# school_shield.net
KiCad netlist of a schematic drawn in EAGLE
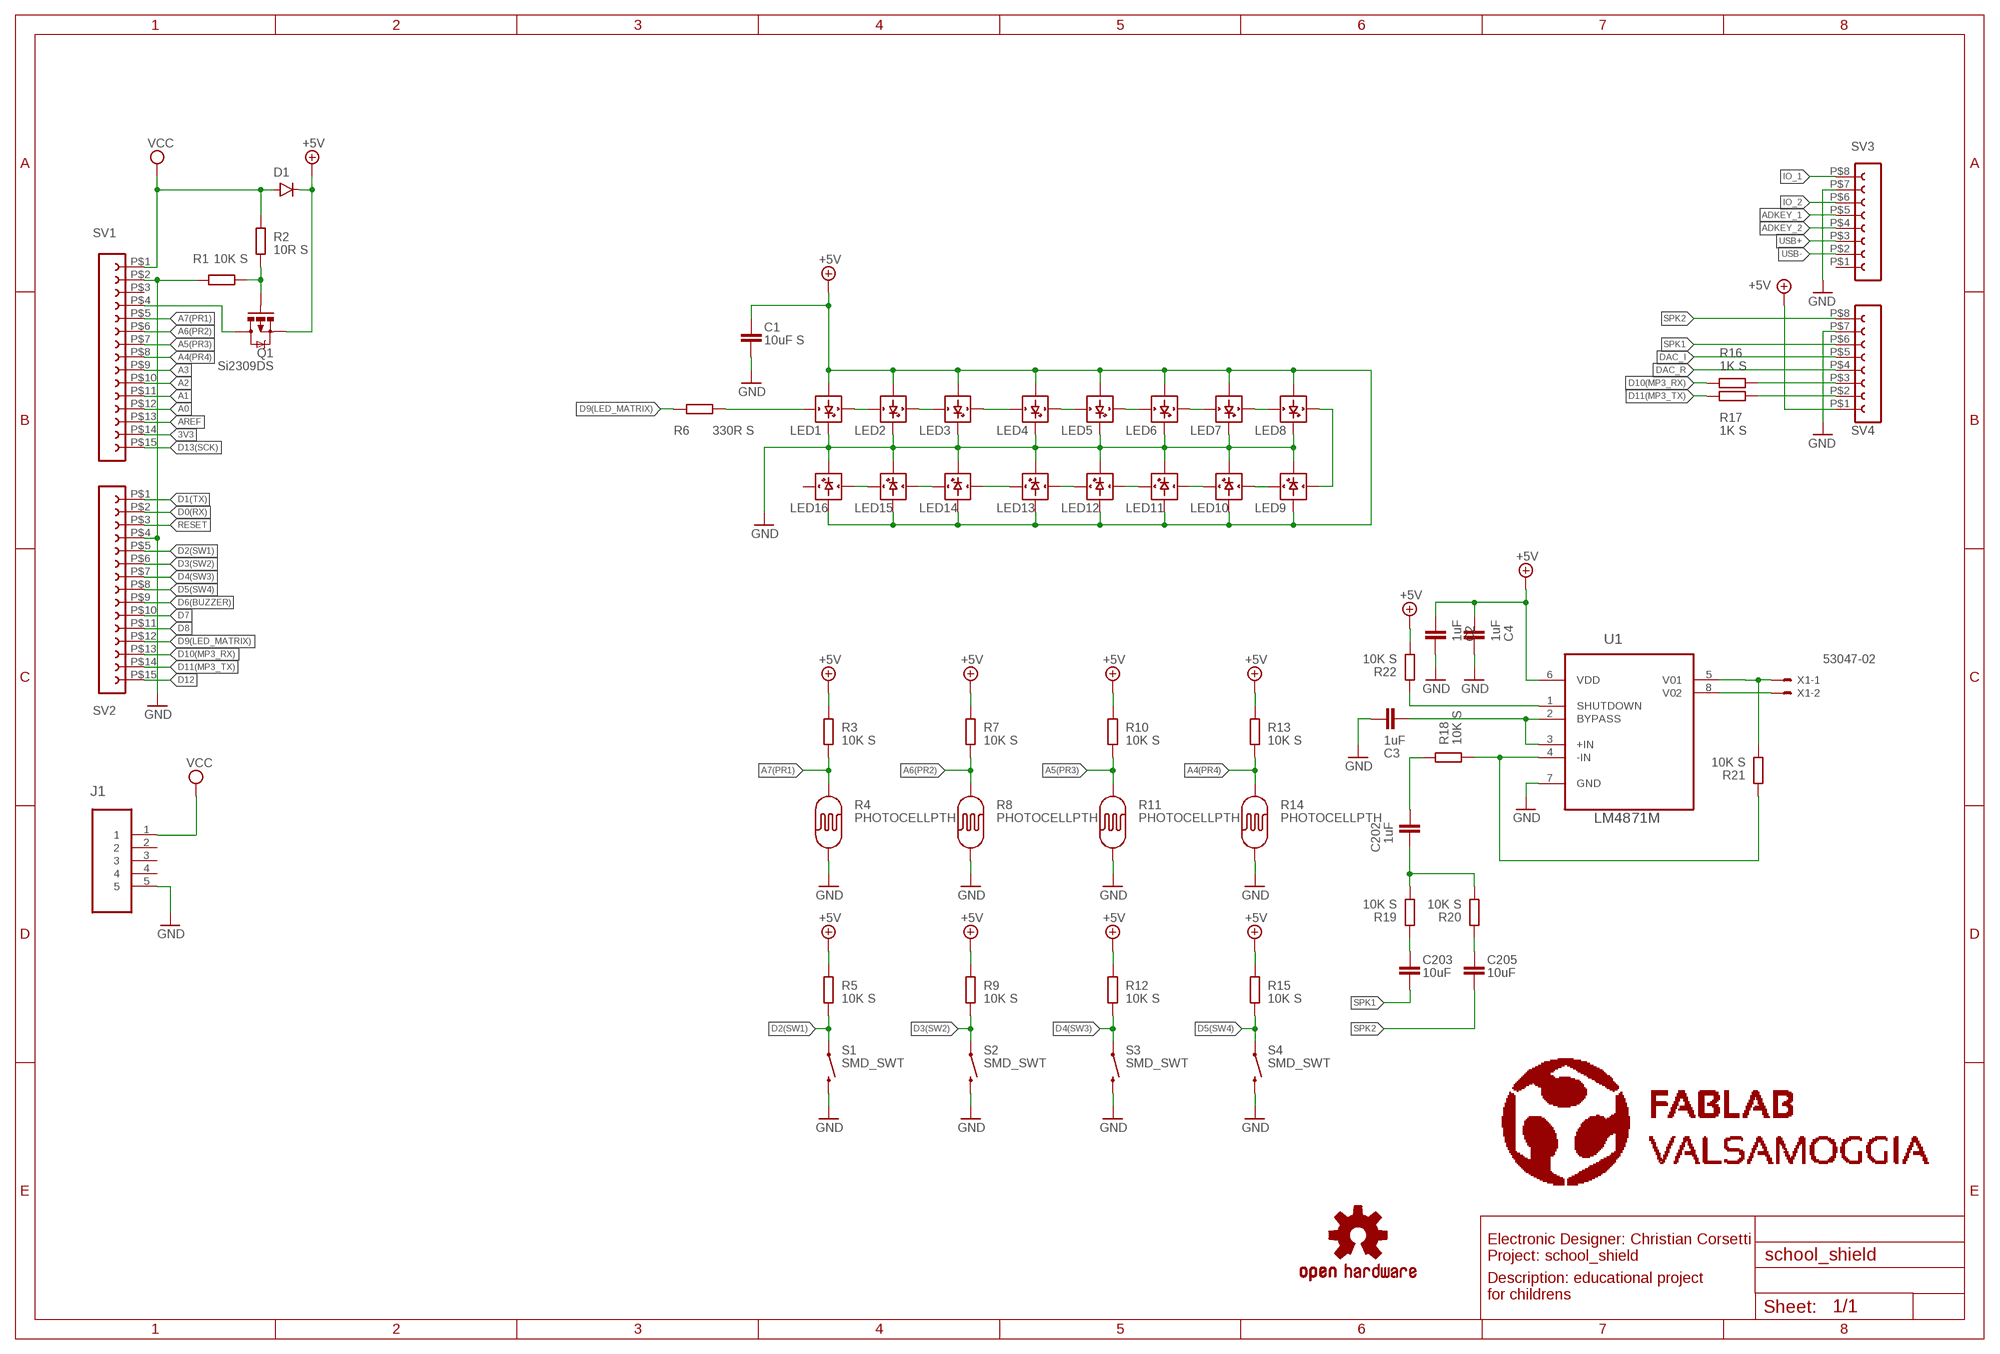
[diagram p0: schematic, sheet 1]

(export (version "E")
  (design (tool "Eeschema 10.0.6"))
  (components
    (comp (ref "C1")
      (value "10uF S")
      (footprint "eagle-import:C0805")
      (libsource (lib "eagle-import") (part "school_shield_1003547_C-EUC0805"))
    )
    (comp (ref "C2")
      (value "1uF")
      (footprint "eagle-import:C0805")
      (libsource (lib "eagle-import") (part "C-EUC0805"))
    )
    (comp (ref "C3")
      (value "1uF")
      (footprint "eagle-import:C0805")
      (libsource (lib "eagle-import") (part "C-EUC0805"))
    )
    (comp (ref "C4")
      (value "1uF")
      (footprint "eagle-import:C0805")
      (libsource (lib "eagle-import") (part "C-EUC0805"))
    )
    (comp (ref "C202")
      (value "1uF")
      (footprint "eagle-import:C0805")
      (libsource (lib "eagle-import") (part "C-EUC0805"))
    )
    (comp (ref "C203")
      (value "10uF")
      (footprint "eagle-import:C0805")
      (libsource (lib "eagle-import") (part "C-EUC0805"))
    )
    (comp (ref "C205")
      (value "10uF")
      (footprint "eagle-import:C0805")
      (libsource (lib "eagle-import") (part "C-EUC0805"))
    )
    (comp (ref "D1")
      (value "DIODESMA")
      (footprint "eagle-import:SMA-DIODE")
      (libsource (lib "eagle-import") (part "DIODESMA"))
    )
    (comp (ref "J1")
      (value "47346-0001")
      (footprint "eagle-import:MOLEX_47346-0001")
      (fields (field (name "SPICEPREFIX") "X"))
      (libsource (lib "eagle-import") (part "47346-0001"))
    )
    (comp (ref "LED1")
      (value "WS2812B_ALT")
      (footprint "eagle-import:WS2812B")
      (libsource (lib "eagle-import") (part "WS2812B_ALT"))
    )
    (comp (ref "LED2")
      (value "WS2812B_ALT")
      (footprint "eagle-import:WS2812B")
      (libsource (lib "eagle-import") (part "WS2812B_ALT"))
    )
    (comp (ref "LED3")
      (value "WS2812B_ALT")
      (footprint "eagle-import:WS2812B")
      (libsource (lib "eagle-import") (part "WS2812B_ALT"))
    )
    (comp (ref "LED4")
      (value "WS2812B_ALT")
      (footprint "eagle-import:WS2812B")
      (libsource (lib "eagle-import") (part "WS2812B_ALT"))
    )
    (comp (ref "LED5")
      (value "WS2812B_ALT")
      (footprint "eagle-import:WS2812B")
      (libsource (lib "eagle-import") (part "WS2812B_ALT"))
    )
    (comp (ref "LED6")
      (value "WS2812B_ALT")
      (footprint "eagle-import:WS2812B")
      (libsource (lib "eagle-import") (part "WS2812B_ALT"))
    )
    (comp (ref "LED7")
      (value "WS2812B_ALT")
      (footprint "eagle-import:WS2812B")
      (libsource (lib "eagle-import") (part "WS2812B_ALT"))
    )
    (comp (ref "LED8")
      (value "WS2812B_ALT")
      (footprint "eagle-import:WS2812B")
      (libsource (lib "eagle-import") (part "WS2812B_ALT"))
    )
    (comp (ref "LED9")
      (value "WS2812B_ALT")
      (footprint "eagle-import:WS2812B")
      (libsource (lib "eagle-import") (part "WS2812B_ALT"))
    )
    (comp (ref "LED10")
      (value "WS2812B_ALT")
      (footprint "eagle-import:WS2812B")
      (libsource (lib "eagle-import") (part "WS2812B_ALT"))
    )
    (comp (ref "LED11")
      (value "WS2812B_ALT")
      (footprint "eagle-import:WS2812B")
      (libsource (lib "eagle-import") (part "WS2812B_ALT"))
    )
    (comp (ref "LED12")
      (value "WS2812B_ALT")
      (footprint "eagle-import:WS2812B")
      (libsource (lib "eagle-import") (part "WS2812B_ALT"))
    )
    (comp (ref "LED13")
      (value "WS2812B_ALT")
      (footprint "eagle-import:WS2812B")
      (libsource (lib "eagle-import") (part "WS2812B_ALT"))
    )
    (comp (ref "LED14")
      (value "WS2812B_ALT")
      (footprint "eagle-import:WS2812B")
      (libsource (lib "eagle-import") (part "WS2812B_ALT"))
    )
    (comp (ref "LED15")
      (value "WS2812B_ALT")
      (footprint "eagle-import:WS2812B")
      (libsource (lib "eagle-import") (part "WS2812B_ALT"))
    )
    (comp (ref "LED16")
      (value "WS2812B_ALT")
      (footprint "eagle-import:WS2812B")
      (libsource (lib "eagle-import") (part "WS2812B_ALT"))
    )
    (comp (ref "LOGO1")
      (value "OSHW-LOGOMINI")
      (footprint "eagle-import:OSHW-LOGO-MINI")
      (libsource (lib "eagle-import") (part "OSHW-LOGOMINI"))
    )
    (comp (ref "Q1")
      (value "Si2309DS")
      (footprint "eagle-import:SOT23-3")
      (libsource (lib "eagle-import") (part "MOSFET-PCHANNELSMD"))
    )
    (comp (ref "R1")
      (value "10K S")
      (footprint "eagle-import:R0805")
      (libsource (lib "eagle-import") (part "R-EU_R0805"))
    )
    (comp (ref "R2")
      (value "10R S")
      (footprint "eagle-import:R0805")
      (libsource (lib "eagle-import") (part "R-EU_R0805"))
    )
    (comp (ref "R3")
      (value "10K S")
      (footprint "eagle-import:R0805")
      (libsource (lib "eagle-import") (part "R-EU_R0805"))
    )
    (comp (ref "R4")
      (value "PHOTOCELLPTH")
      (footprint "eagle-import:PHOTOCELL")
      (libsource (lib "eagle-import") (part "PHOTOCELLPTH"))
    )
    (comp (ref "R5")
      (value "10K S")
      (footprint "eagle-import:R0805")
      (libsource (lib "eagle-import") (part "R-EU_R0805"))
    )
    (comp (ref "R6")
      (value "330R S")
      (footprint "eagle-import:R0805")
      (libsource (lib "eagle-import") (part "R-EU_R0805"))
    )
    (comp (ref "R7")
      (value "10K S")
      (footprint "eagle-import:R0805")
      (libsource (lib "eagle-import") (part "R-EU_R0805"))
    )
    (comp (ref "R8")
      (value "PHOTOCELLPTH")
      (footprint "eagle-import:PHOTOCELL")
      (libsource (lib "eagle-import") (part "PHOTOCELLPTH"))
    )
    (comp (ref "R9")
      (value "10K S")
      (footprint "eagle-import:R0805")
      (libsource (lib "eagle-import") (part "R-EU_R0805"))
    )
    (comp (ref "R10")
      (value "10K S")
      (footprint "eagle-import:R0805")
      (libsource (lib "eagle-import") (part "R-EU_R0805"))
    )
    (comp (ref "R11")
      (value "PHOTOCELLPTH")
      (footprint "eagle-import:PHOTOCELL")
      (libsource (lib "eagle-import") (part "PHOTOCELLPTH"))
    )
    (comp (ref "R12")
      (value "10K S")
      (footprint "eagle-import:R0805")
      (libsource (lib "eagle-import") (part "R-EU_R0805"))
    )
    (comp (ref "R13")
      (value "10K S")
      (footprint "eagle-import:R0805")
      (libsource (lib "eagle-import") (part "R-EU_R0805"))
    )
    (comp (ref "R14")
      (value "PHOTOCELLPTH")
      (footprint "eagle-import:PHOTOCELL")
      (libsource (lib "eagle-import") (part "PHOTOCELLPTH"))
    )
    (comp (ref "R15")
      (value "10K S")
      (footprint "eagle-import:R0805")
      (libsource (lib "eagle-import") (part "R-EU_R0805"))
    )
    (comp (ref "R16")
      (value "1K S")
      (footprint "eagle-import:R0805")
      (libsource (lib "eagle-import") (part "R-EU_R0805"))
    )
    (comp (ref "R17")
      (value "1K S")
      (footprint "eagle-import:R0805")
      (libsource (lib "eagle-import") (part "R-EU_R0805"))
    )
    (comp (ref "R18")
      (value "10K S")
      (footprint "eagle-import:R0805")
      (libsource (lib "eagle-import") (part "R-EU_R0805"))
    )
    (comp (ref "R19")
      (value "10K S")
      (footprint "eagle-import:R0805")
      (libsource (lib "eagle-import") (part "R-EU_R0805"))
    )
    (comp (ref "R20")
      (value "10K S")
      (footprint "eagle-import:R0805")
      (libsource (lib "eagle-import") (part "R-EU_R0805"))
    )
    (comp (ref "R21")
      (value "10K S")
      (footprint "eagle-import:R0805")
      (libsource (lib "eagle-import") (part "R-EU_R0805"))
    )
    (comp (ref "R22")
      (value "10K S")
      (footprint "eagle-import:R0805")
      (libsource (lib "eagle-import") (part "R-EU_R0805"))
    )
    (comp (ref "S1")
      (value "SMD_SWT")
      (footprint "eagle-import:TACTILE_SWITCH_TALL")
      (libsource (lib "eagle-import") (part "SWITCH-MOMENTARY-2SMD-4"))
    )
    (comp (ref "S2")
      (value "SMD_SWT")
      (footprint "eagle-import:TACTILE_SWITCH_TALL")
      (libsource (lib "eagle-import") (part "SWITCH-MOMENTARY-2SMD-4"))
    )
    (comp (ref "S3")
      (value "SMD_SWT")
      (footprint "eagle-import:TACTILE_SWITCH_TALL")
      (libsource (lib "eagle-import") (part "SWITCH-MOMENTARY-2SMD-4"))
    )
    (comp (ref "S4")
      (value "SMD_SWT")
      (footprint "eagle-import:TACTILE_SWITCH_TALL")
      (libsource (lib "eagle-import") (part "SWITCH-MOMENTARY-2SMD-4"))
    )
    (comp (ref "SV1")
      (value "FE15-1SMD")
      (footprint "eagle-import:FE15_SMD")
      (libsource (lib "eagle-import") (part "FE15-1SMD"))
    )
    (comp (ref "SV2")
      (value "FE15-1SMD")
      (footprint "eagle-import:FE15_SMD")
      (libsource (lib "eagle-import") (part "FE15-1SMD"))
    )
    (comp (ref "SV3")
      (value "FE08-1SMD")
      (footprint "eagle-import:FE08_SMD")
      (libsource (lib "eagle-import") (part "FE08-1SMD"))
    )
    (comp (ref "SV4")
      (value "FE08-1SMD")
      (footprint "eagle-import:FE08_SMD")
      (libsource (lib "eagle-import") (part "FE08-1SMD"))
    )
    (comp (ref "U$1")
      (value "FABLAB")
      (footprint "eagle-import:FABLAB")
      (libsource (lib "eagle-import") (part "FABLAB"))
    )
    (comp (ref "U1")
      (value "LM4871M")
      (footprint "eagle-import:SOIC127P600X175-8N")
      (libsource (lib "eagle-import") (part "LM4871M"))
    )
    (comp (ref "X1")
      (value "53047-02")
      (footprint "eagle-import:53047-02")
      (libsource (lib "eagle-import") (part "53?-02047"))
    )
  )
  (nets
    (net (code "1") (name "+5V") (class "Default")
      (node (ref "C1") (pin "2") (pinfunction "2_2") (pintype "passive"))
      (node (ref "C2") (pin "1") (pinfunction "1_1") (pintype "passive"))
      (node (ref "C4") (pin "1") (pinfunction "1_1") (pintype "passive"))
      (node (ref "D1") (pin "C") (pinfunction "C_C") (pintype "passive"))
      (node (ref "LED1") (pin "1-VDD") (pinfunction "VDD_1-VDD") (pintype "bidirectional"))
      (node (ref "LED10") (pin "1-VDD") (pinfunction "VDD_1-VDD") (pintype "bidirectional"))
      (node (ref "LED11") (pin "1-VDD") (pinfunction "VDD_1-VDD") (pintype "bidirectional"))
      (node (ref "LED12") (pin "1-VDD") (pinfunction "VDD_1-VDD") (pintype "bidirectional"))
      (node (ref "LED13") (pin "1-VDD") (pinfunction "VDD_1-VDD") (pintype "bidirectional"))
      (node (ref "LED14") (pin "1-VDD") (pinfunction "VDD_1-VDD") (pintype "bidirectional"))
      (node (ref "LED15") (pin "1-VDD") (pinfunction "VDD_1-VDD") (pintype "bidirectional"))
      (node (ref "LED16") (pin "1-VDD") (pinfunction "VDD_1-VDD") (pintype "bidirectional"))
      (node (ref "LED2") (pin "1-VDD") (pinfunction "VDD_1-VDD") (pintype "bidirectional"))
      (node (ref "LED3") (pin "1-VDD") (pinfunction "VDD_1-VDD") (pintype "bidirectional"))
      (node (ref "LED4") (pin "1-VDD") (pinfunction "VDD_1-VDD") (pintype "bidirectional"))
      (node (ref "LED5") (pin "1-VDD") (pinfunction "VDD_1-VDD") (pintype "bidirectional"))
      (node (ref "LED6") (pin "1-VDD") (pinfunction "VDD_1-VDD") (pintype "bidirectional"))
      (node (ref "LED7") (pin "1-VDD") (pinfunction "VDD_1-VDD") (pintype "bidirectional"))
      (node (ref "LED8") (pin "1-VDD") (pinfunction "VDD_1-VDD") (pintype "bidirectional"))
      (node (ref "LED9") (pin "1-VDD") (pinfunction "VDD_1-VDD") (pintype "bidirectional"))
      (node (ref "Q1") (pin "2") (pinfunction "S_2") (pintype "passive"))
      (node (ref "R10") (pin "2") (pinfunction "2_2") (pintype "passive"))
      (node (ref "R12") (pin "2") (pinfunction "2_2") (pintype "passive"))
      (node (ref "R13") (pin "2") (pinfunction "2_2") (pintype "passive"))
      (node (ref "R15") (pin "2") (pinfunction "2_2") (pintype "passive"))
      (node (ref "R22") (pin "1") (pinfunction "1_1") (pintype "passive"))
      (node (ref "R3") (pin "2") (pinfunction "2_2") (pintype "passive"))
      (node (ref "R5") (pin "2") (pinfunction "2_2") (pintype "passive"))
      (node (ref "R7") (pin "2") (pinfunction "2_2") (pintype "passive"))
      (node (ref "R9") (pin "2") (pinfunction "2_2") (pintype "passive"))
      (node (ref "SV4") (pin "P$1") (pinfunction "1_P$1") (pintype "passive"))
      (node (ref "U1") (pin "6") (pinfunction "VDD_6") (pintype "power_in"))
    )
    (net (code "2") (name "3V3") (class "Default")
      (node (ref "SV1") (pin "P$14") (pinfunction "14_P$14") (pintype "passive"))
    )
    (net (code "3") (name "A0") (class "Default")
      (node (ref "SV1") (pin "P$12") (pinfunction "12_P$12") (pintype "passive"))
    )
    (net (code "4") (name "A1") (class "Default")
      (node (ref "SV1") (pin "P$11") (pinfunction "11_P$11") (pintype "passive"))
    )
    (net (code "5") (name "A2") (class "Default")
      (node (ref "SV1") (pin "P$10") (pinfunction "10_P$10") (pintype "passive"))
    )
    (net (code "6") (name "A3") (class "Default")
      (node (ref "SV1") (pin "P$9") (pinfunction "9_P$9") (pintype "passive"))
    )
    (net (code "7") (name "A4(PR4)") (class "Default")
      (node (ref "R13") (pin "1") (pinfunction "1_1") (pintype "passive"))
      (node (ref "R14") (pin "2") (pinfunction "P$2_2") (pintype "bidirectional"))
      (node (ref "SV1") (pin "P$8") (pinfunction "8_P$8") (pintype "passive"))
    )
    (net (code "8") (name "A5(PR3)") (class "Default")
      (node (ref "R10") (pin "1") (pinfunction "1_1") (pintype "passive"))
      (node (ref "R11") (pin "2") (pinfunction "P$2_2") (pintype "bidirectional"))
      (node (ref "SV1") (pin "P$7") (pinfunction "7_P$7") (pintype "passive"))
    )
    (net (code "9") (name "A6(PR2)") (class "Default")
      (node (ref "R7") (pin "1") (pinfunction "1_1") (pintype "passive"))
      (node (ref "R8") (pin "2") (pinfunction "P$2_2") (pintype "bidirectional"))
      (node (ref "SV1") (pin "P$6") (pinfunction "6_P$6") (pintype "passive"))
    )
    (net (code "10") (name "A7(PR1)") (class "Default")
      (node (ref "R3") (pin "1") (pinfunction "1_1") (pintype "passive"))
      (node (ref "R4") (pin "2") (pinfunction "P$2_2") (pintype "bidirectional"))
      (node (ref "SV1") (pin "P$5") (pinfunction "5_P$5") (pintype "passive"))
    )
    (net (code "11") (name "ADKEY_1") (class "Default")
      (node (ref "SV3") (pin "P$5") (pinfunction "5_P$5") (pintype "passive"))
    )
    (net (code "12") (name "ADKEY_2") (class "Default")
      (node (ref "SV3") (pin "P$4") (pinfunction "4_P$4") (pintype "passive"))
    )
    (net (code "13") (name "AREF") (class "Default")
      (node (ref "SV1") (pin "P$13") (pinfunction "13_P$13") (pintype "passive"))
    )
    (net (code "14") (name "D0(RX)") (class "Default")
      (node (ref "SV2") (pin "P$2") (pinfunction "2_P$2") (pintype "passive"))
    )
    (net (code "15") (name "D1(TX)") (class "Default")
      (node (ref "SV2") (pin "P$1") (pinfunction "1_P$1") (pintype "passive"))
    )
    (net (code "16") (name "D2(SW1)") (class "Default")
      (node (ref "R5") (pin "1") (pinfunction "1_1") (pintype "passive"))
      (node (ref "S1") (pin "A2") (pinfunction "1_A2") (pintype "passive"))
      (node (ref "SV2") (pin "P$5") (pinfunction "5_P$5") (pintype "passive"))
    )
    (net (code "17") (name "D3(SW2)") (class "Default")
      (node (ref "R9") (pin "1") (pinfunction "1_1") (pintype "passive"))
      (node (ref "S2") (pin "A2") (pinfunction "1_A2") (pintype "passive"))
      (node (ref "SV2") (pin "P$6") (pinfunction "6_P$6") (pintype "passive"))
    )
    (net (code "18") (name "D4(SW3)") (class "Default")
      (node (ref "R12") (pin "1") (pinfunction "1_1") (pintype "passive"))
      (node (ref "S3") (pin "A2") (pinfunction "1_A2") (pintype "passive"))
      (node (ref "SV2") (pin "P$7") (pinfunction "7_P$7") (pintype "passive"))
    )
    (net (code "19") (name "D5(SW4)") (class "Default")
      (node (ref "R15") (pin "1") (pinfunction "1_1") (pintype "passive"))
      (node (ref "S4") (pin "A2") (pinfunction "1_A2") (pintype "passive"))
      (node (ref "SV2") (pin "P$8") (pinfunction "8_P$8") (pintype "passive"))
    )
    (net (code "20") (name "D6(BUZZER)") (class "Default")
      (node (ref "SV2") (pin "P$9") (pinfunction "9_P$9") (pintype "passive"))
    )
    (net (code "21") (name "D7") (class "Default")
      (node (ref "SV2") (pin "P$10") (pinfunction "10_P$10") (pintype "passive"))
    )
    (net (code "22") (name "D8") (class "Default")
      (node (ref "SV2") (pin "P$11") (pinfunction "11_P$11") (pintype "passive"))
    )
    (net (code "23") (name "D9(LED_MATRIX)") (class "Default")
      (node (ref "R6") (pin "2") (pinfunction "2_2") (pintype "passive"))
      (node (ref "SV2") (pin "P$12") (pinfunction "12_P$12") (pintype "passive"))
    )
    (net (code "24") (name "D10(MP3_RX)") (class "Default")
      (node (ref "R16") (pin "2") (pinfunction "2_2") (pintype "passive"))
      (node (ref "SV2") (pin "P$13") (pinfunction "13_P$13") (pintype "passive"))
    )
    (net (code "25") (name "D11(MP3_TX)") (class "Default")
      (node (ref "R17") (pin "2") (pinfunction "2_2") (pintype "passive"))
      (node (ref "SV2") (pin "P$14") (pinfunction "14_P$14") (pintype "passive"))
    )
    (net (code "26") (name "D12") (class "Default")
      (node (ref "SV2") (pin "P$15") (pinfunction "15_P$15") (pintype "passive"))
    )
    (net (code "27") (name "D13(SCK)") (class "Default")
      (node (ref "SV1") (pin "P$15") (pinfunction "15_P$15") (pintype "passive"))
    )
    (net (code "28") (name "DAC_I") (class "Default")
      (node (ref "SV4") (pin "P$5") (pinfunction "5_P$5") (pintype "passive"))
    )
    (net (code "29") (name "DAC_R") (class "Default")
      (node (ref "SV4") (pin "P$4") (pinfunction "4_P$4") (pintype "passive"))
    )
    (net (code "30") (name "GND") (class "Default")
      (node (ref "C1") (pin "1") (pinfunction "1_1") (pintype "passive"))
      (node (ref "C2") (pin "2") (pinfunction "2_2") (pintype "passive"))
      (node (ref "C3") (pin "2") (pinfunction "2_2") (pintype "passive"))
      (node (ref "C4") (pin "2") (pinfunction "2_2") (pintype "passive"))
      (node (ref "J1") (pin "5") (pinfunction "5_5") (pintype "input"))
      (node (ref "LED1") (pin "3-GND") (pinfunction "GND_3-GND") (pintype "bidirectional"))
      (node (ref "LED10") (pin "3-GND") (pinfunction "GND_3-GND") (pintype "bidirectional"))
      (node (ref "LED11") (pin "3-GND") (pinfunction "GND_3-GND") (pintype "bidirectional"))
      (node (ref "LED12") (pin "3-GND") (pinfunction "GND_3-GND") (pintype "bidirectional"))
      (node (ref "LED13") (pin "3-GND") (pinfunction "GND_3-GND") (pintype "bidirectional"))
      (node (ref "LED14") (pin "3-GND") (pinfunction "GND_3-GND") (pintype "bidirectional"))
      (node (ref "LED15") (pin "3-GND") (pinfunction "GND_3-GND") (pintype "bidirectional"))
      (node (ref "LED16") (pin "3-GND") (pinfunction "GND_3-GND") (pintype "bidirectional"))
      (node (ref "LED2") (pin "3-GND") (pinfunction "GND_3-GND") (pintype "bidirectional"))
      (node (ref "LED3") (pin "3-GND") (pinfunction "GND_3-GND") (pintype "bidirectional"))
      (node (ref "LED4") (pin "3-GND") (pinfunction "GND_3-GND") (pintype "bidirectional"))
      (node (ref "LED5") (pin "3-GND") (pinfunction "GND_3-GND") (pintype "bidirectional"))
      (node (ref "LED6") (pin "3-GND") (pinfunction "GND_3-GND") (pintype "bidirectional"))
      (node (ref "LED7") (pin "3-GND") (pinfunction "GND_3-GND") (pintype "bidirectional"))
      (node (ref "LED8") (pin "3-GND") (pinfunction "GND_3-GND") (pintype "bidirectional"))
      (node (ref "LED9") (pin "3-GND") (pinfunction "GND_3-GND") (pintype "bidirectional"))
      (node (ref "R1") (pin "2") (pinfunction "2_2") (pintype "passive"))
      (node (ref "R11") (pin "1") (pinfunction "P$1_1") (pintype "bidirectional"))
      (node (ref "R14") (pin "1") (pinfunction "P$1_1") (pintype "bidirectional"))
      (node (ref "R4") (pin "1") (pinfunction "P$1_1") (pintype "bidirectional"))
      (node (ref "R8") (pin "1") (pinfunction "P$1_1") (pintype "bidirectional"))
      (node (ref "S1") (pin "B2") (pinfunction "2_B2") (pintype "passive"))
      (node (ref "S2") (pin "B2") (pinfunction "2_B2") (pintype "passive"))
      (node (ref "S3") (pin "B2") (pinfunction "2_B2") (pintype "passive"))
      (node (ref "S4") (pin "B2") (pinfunction "2_B2") (pintype "passive"))
      (node (ref "SV1") (pin "P$2") (pinfunction "2_P$2") (pintype "passive"))
      (node (ref "SV2") (pin "P$4") (pinfunction "4_P$4") (pintype "passive"))
      (node (ref "SV3") (pin "P$7") (pinfunction "7_P$7") (pintype "passive"))
      (node (ref "SV4") (pin "P$7") (pinfunction "7_P$7") (pintype "passive"))
      (node (ref "U1") (pin "7") (pinfunction "GND_7") (pintype "passive"))
    )
    (net (code "31") (name "IO_1") (class "Default")
      (node (ref "SV3") (pin "P$8") (pinfunction "8_P$8") (pintype "passive"))
    )
    (net (code "32") (name "IO_2") (class "Default")
      (node (ref "SV3") (pin "P$6") (pinfunction "6_P$6") (pintype "passive"))
    )
    (net (code "33") (name "Net-(C202-Pad1)") (class "Default")
      (node (ref "C202") (pin "1") (pinfunction "1_1") (pintype "passive"))
      (node (ref "R19") (pin "1") (pinfunction "1_1") (pintype "passive"))
      (node (ref "R20") (pin "1") (pinfunction "1_1") (pintype "passive"))
    )
    (net (code "34") (name "Net-(C202-Pad2)") (class "Default")
      (node (ref "C202") (pin "2") (pinfunction "2_2") (pintype "passive"))
      (node (ref "R18") (pin "2") (pinfunction "2_2") (pintype "passive"))
    )
    (net (code "35") (name "Net-(C203-Pad1)") (class "Default")
      (node (ref "C203") (pin "1") (pinfunction "1_1") (pintype "passive"))
      (node (ref "R19") (pin "2") (pinfunction "2_2") (pintype "passive"))
    )
    (net (code "36") (name "Net-(C205-Pad1)") (class "Default")
      (node (ref "C205") (pin "1") (pinfunction "1_1") (pintype "passive"))
      (node (ref "R20") (pin "2") (pinfunction "2_2") (pintype "passive"))
    )
    (net (code "37") (name "Net-(LED1-DIN)") (class "Default")
      (node (ref "LED1") (pin "4-DIN") (pinfunction "DIN_4-DIN") (pintype "input"))
      (node (ref "R6") (pin "1") (pinfunction "1_1") (pintype "passive"))
    )
    (net (code "38") (name "Net-(LED1-DOUT)") (class "Default")
      (node (ref "LED1") (pin "2-DOUT") (pinfunction "DOUT_2-DOUT") (pintype "output"))
      (node (ref "LED2") (pin "4-DIN") (pinfunction "DIN_4-DIN") (pintype "input"))
    )
    (net (code "39") (name "Net-(LED2-DOUT)") (class "Default")
      (node (ref "LED2") (pin "2-DOUT") (pinfunction "DOUT_2-DOUT") (pintype "output"))
      (node (ref "LED3") (pin "4-DIN") (pinfunction "DIN_4-DIN") (pintype "input"))
    )
    (net (code "40") (name "Net-(LED3-DOUT)") (class "Default")
      (node (ref "LED3") (pin "2-DOUT") (pinfunction "DOUT_2-DOUT") (pintype "output"))
      (node (ref "LED4") (pin "4-DIN") (pinfunction "DIN_4-DIN") (pintype "input"))
    )
    (net (code "41") (name "Net-(LED4-DOUT)") (class "Default")
      (node (ref "LED4") (pin "2-DOUT") (pinfunction "DOUT_2-DOUT") (pintype "output"))
      (node (ref "LED5") (pin "4-DIN") (pinfunction "DIN_4-DIN") (pintype "input"))
    )
    (net (code "42") (name "Net-(LED5-DOUT)") (class "Default")
      (node (ref "LED5") (pin "2-DOUT") (pinfunction "DOUT_2-DOUT") (pintype "output"))
      (node (ref "LED6") (pin "4-DIN") (pinfunction "DIN_4-DIN") (pintype "input"))
    )
    (net (code "43") (name "Net-(LED6-DOUT)") (class "Default")
      (node (ref "LED6") (pin "2-DOUT") (pinfunction "DOUT_2-DOUT") (pintype "output"))
      (node (ref "LED7") (pin "4-DIN") (pinfunction "DIN_4-DIN") (pintype "input"))
    )
    (net (code "44") (name "Net-(LED7-DOUT)") (class "Default")
      (node (ref "LED7") (pin "2-DOUT") (pinfunction "DOUT_2-DOUT") (pintype "output"))
      (node (ref "LED8") (pin "4-DIN") (pinfunction "DIN_4-DIN") (pintype "input"))
    )
    (net (code "45") (name "Net-(LED8-DOUT)") (class "Default")
      (node (ref "LED8") (pin "2-DOUT") (pinfunction "DOUT_2-DOUT") (pintype "output"))
      (node (ref "LED9") (pin "4-DIN") (pinfunction "DIN_4-DIN") (pintype "input"))
    )
    (net (code "46") (name "Net-(LED10-DIN)") (class "Default")
      (node (ref "LED10") (pin "4-DIN") (pinfunction "DIN_4-DIN") (pintype "input"))
      (node (ref "LED9") (pin "2-DOUT") (pinfunction "DOUT_2-DOUT") (pintype "output"))
    )
    (net (code "47") (name "Net-(LED10-DOUT)") (class "Default")
      (node (ref "LED10") (pin "2-DOUT") (pinfunction "DOUT_2-DOUT") (pintype "output"))
      (node (ref "LED11") (pin "4-DIN") (pinfunction "DIN_4-DIN") (pintype "input"))
    )
    (net (code "48") (name "Net-(LED11-DOUT)") (class "Default")
      (node (ref "LED11") (pin "2-DOUT") (pinfunction "DOUT_2-DOUT") (pintype "output"))
      (node (ref "LED12") (pin "4-DIN") (pinfunction "DIN_4-DIN") (pintype "input"))
    )
    (net (code "49") (name "Net-(LED12-DOUT)") (class "Default")
      (node (ref "LED12") (pin "2-DOUT") (pinfunction "DOUT_2-DOUT") (pintype "output"))
      (node (ref "LED13") (pin "4-DIN") (pinfunction "DIN_4-DIN") (pintype "input"))
    )
    (net (code "50") (name "Net-(LED13-DOUT)") (class "Default")
      (node (ref "LED13") (pin "2-DOUT") (pinfunction "DOUT_2-DOUT") (pintype "output"))
      (node (ref "LED14") (pin "4-DIN") (pinfunction "DIN_4-DIN") (pintype "input"))
    )
    (net (code "51") (name "Net-(LED14-DOUT)") (class "Default")
      (node (ref "LED14") (pin "2-DOUT") (pinfunction "DOUT_2-DOUT") (pintype "output"))
      (node (ref "LED15") (pin "4-DIN") (pinfunction "DIN_4-DIN") (pintype "input"))
    )
    (net (code "52") (name "Net-(LED15-DOUT)") (class "Default")
      (node (ref "LED15") (pin "2-DOUT") (pinfunction "DOUT_2-DOUT") (pintype "output"))
      (node (ref "LED16") (pin "4-DIN") (pinfunction "DIN_4-DIN") (pintype "input"))
    )
    (net (code "53") (name "Net-(Q1-D)") (class "Default")
      (node (ref "Q1") (pin "3") (pinfunction "D_3") (pintype "passive"))
      (node (ref "SV1") (pin "P$4") (pinfunction "4_P$4") (pintype "passive"))
    )
    (net (code "54") (name "Net-(Q1-G)") (class "Default")
      (node (ref "Q1") (pin "1") (pinfunction "G_1") (pintype "passive"))
      (node (ref "R1") (pin "1") (pinfunction "1_1") (pintype "passive"))
      (node (ref "R2") (pin "2") (pinfunction "2_2") (pintype "passive"))
    )
    (net (code "55") (name "Net-(SV4-2)") (class "Default")
      (node (ref "R17") (pin "1") (pinfunction "1_1") (pintype "passive"))
      (node (ref "SV4") (pin "P$2") (pinfunction "2_P$2") (pintype "passive"))
    )
    (net (code "56") (name "Net-(SV4-3)") (class "Default")
      (node (ref "R16") (pin "1") (pinfunction "1_1") (pintype "passive"))
      (node (ref "SV4") (pin "P$3") (pinfunction "3_P$3") (pintype "passive"))
    )
    (net (code "57") (name "Net-(U1-+IN)") (class "Default")
      (node (ref "C3") (pin "1") (pinfunction "1_1") (pintype "passive"))
      (node (ref "U1") (pin "2") (pinfunction "BYPASS_2") (pintype "input"))
      (node (ref "U1") (pin "3") (pinfunction "+IN_3") (pintype "input"))
    )
    (net (code "58") (name "Net-(U1--IN)") (class "Default")
      (node (ref "R18") (pin "1") (pinfunction "1_1") (pintype "passive"))
      (node (ref "R21") (pin "2") (pinfunction "2_2") (pintype "passive"))
      (node (ref "U1") (pin "4") (pinfunction "-IN_4") (pintype "input"))
    )
    (net (code "59") (name "Net-(U1-SHUTDOWN)") (class "Default")
      (node (ref "R22") (pin "2") (pinfunction "2_2") (pintype "passive"))
      (node (ref "U1") (pin "1") (pinfunction "SHUTDOWN_1") (pintype "input"))
    )
    (net (code "60") (name "Net-(U1-V01)") (class "Default")
      (node (ref "R21") (pin "1") (pinfunction "1_1") (pintype "passive"))
      (node (ref "U1") (pin "5") (pinfunction "V01_5") (pintype "output"))
      (node (ref "X1") (pin "1") (pinfunction "S_1") (pintype "passive"))
    )
    (net (code "61") (name "Net-(U1-V02)") (class "Default")
      (node (ref "U1") (pin "8") (pinfunction "V02_8") (pintype "output"))
      (node (ref "X1") (pin "2") (pinfunction "S_2") (pintype "passive"))
    )
    (net (code "62") (name "RESET") (class "Default")
      (node (ref "SV2") (pin "P$3") (pinfunction "3_P$3") (pintype "passive"))
    )
    (net (code "63") (name "SPK1") (class "Default")
      (node (ref "C203") (pin "2") (pinfunction "2_2") (pintype "passive"))
      (node (ref "SV4") (pin "P$6") (pinfunction "6_P$6") (pintype "passive"))
    )
    (net (code "64") (name "SPK2") (class "Default")
      (node (ref "C205") (pin "2") (pinfunction "2_2") (pintype "passive"))
      (node (ref "SV4") (pin "P$8") (pinfunction "8_P$8") (pintype "passive"))
    )
    (net (code "65") (name "USB+") (class "Default")
      (node (ref "SV3") (pin "P$3") (pinfunction "3_P$3") (pintype "passive"))
    )
    (net (code "66") (name "USB-") (class "Default")
      (node (ref "SV3") (pin "P$2") (pinfunction "2_P$2") (pintype "passive"))
    )
    (net (code "67") (name "VCC") (class "Default")
      (node (ref "D1") (pin "A") (pinfunction "A_A") (pintype "passive"))
      (node (ref "J1") (pin "1") (pinfunction "1_1") (pintype "input"))
      (node (ref "R2") (pin "1") (pinfunction "1_1") (pintype "passive"))
      (node (ref "SV1") (pin "P$1") (pinfunction "1_P$1") (pintype "passive"))
    )
    (net (code "68") (name "unconnected-(J1-Pad2)") (class "Default")
      (node (ref "J1") (pin "2") (pinfunction "2_2") (pintype "input"))
    )
    (net (code "69") (name "unconnected-(J1-Pad3)") (class "Default")
      (node (ref "J1") (pin "3") (pinfunction "3_3") (pintype "input"))
    )
    (net (code "70") (name "unconnected-(J1-Pad4)") (class "Default")
      (node (ref "J1") (pin "4") (pinfunction "4_4") (pintype "input"))
    )
    (net (code "71") (name "unconnected-(LED16-DOUT-Pad2-DOUT)") (class "Default")
      (node (ref "LED16") (pin "2-DOUT") (pinfunction "DOUT_2-DOUT") (pintype "output"))
    )
    (net (code "72") (name "unconnected-(SV1-3-PadP$3)") (class "Default")
      (node (ref "SV1") (pin "P$3") (pinfunction "3_P$3") (pintype "passive"))
    )
    (net (code "73") (name "unconnected-(SV3-1-PadP$1)") (class "Default")
      (node (ref "SV3") (pin "P$1") (pinfunction "1_P$1") (pintype "passive"))
    )
  )
)
